# AirCond_P1_V2_0.net
KiCad netlist of a schematic drawn in Altium Designer
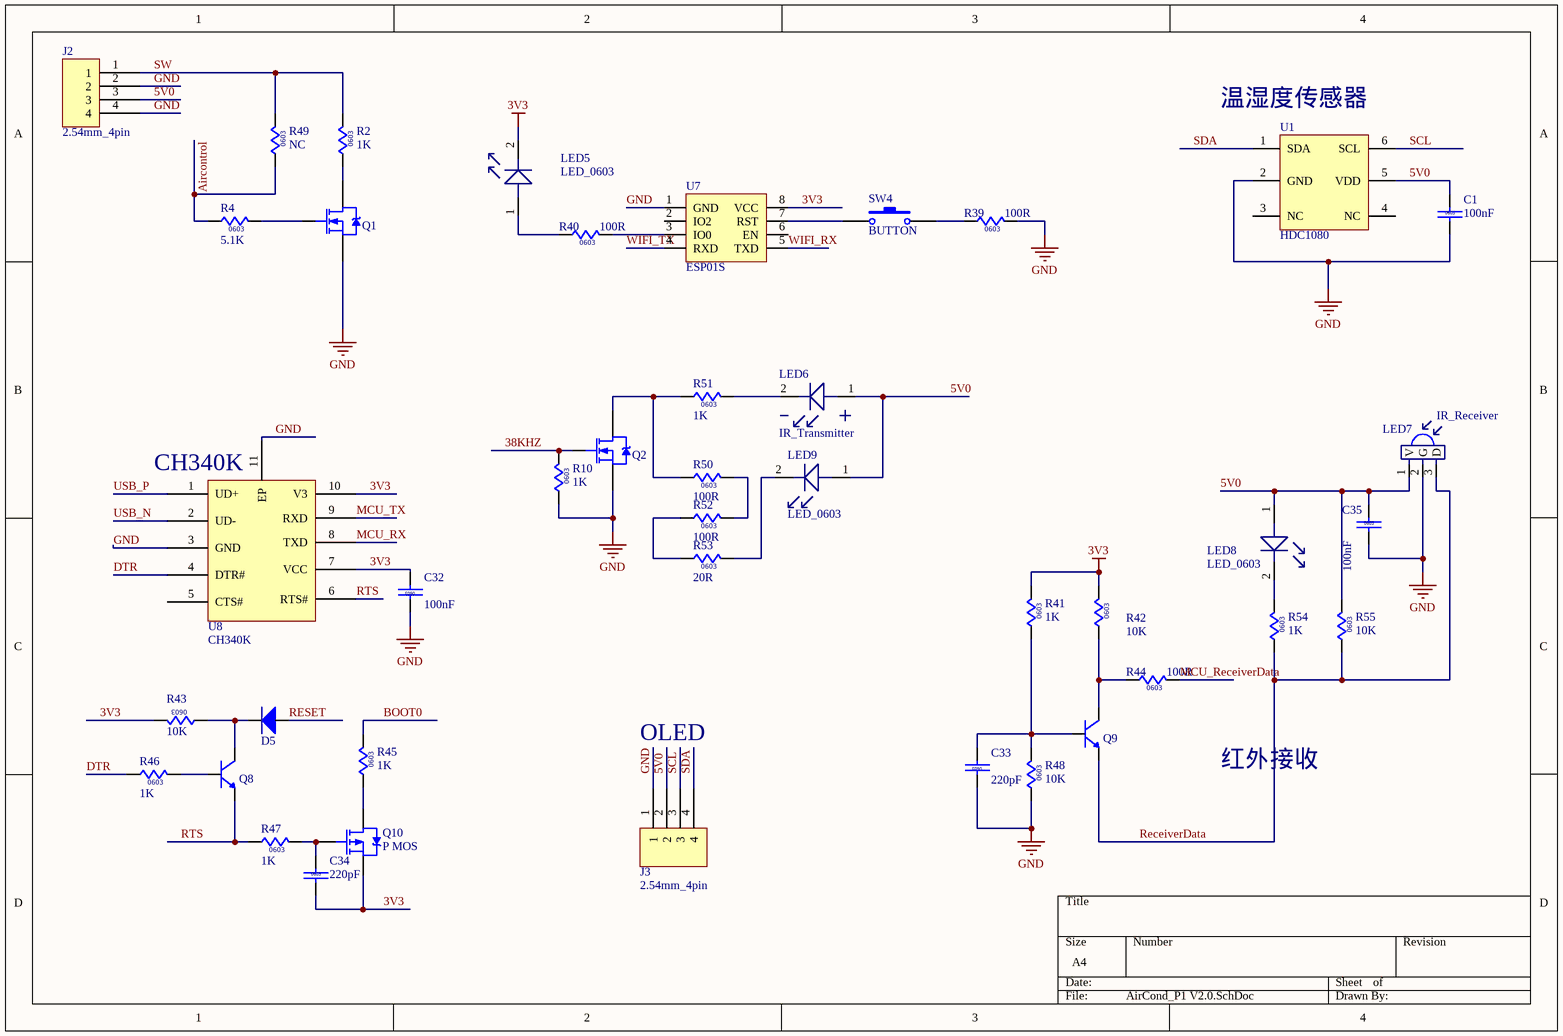
[diagram p0: AirCond_P1 V2.0.SchDoc]

(export (version "E")
  (design (tool "Eeschema 10.0.6"))
  (components
    (comp (ref "C1") (value "100nF") (footprint "0603/CAP") (libsource (lib "ZWC") (part "CAP/0603")))
    (comp (ref "C32") (value "100nF") (footprint "0603/CAP") (libsource (lib "ZWC") (part "CAP/0603")))
    (comp (ref "C33") (value "220pF") (footprint "0603/CAP") (libsource (lib "ZWC") (part "CAP/0603")))
    (comp (ref "C34") (value "220pF") (footprint "0603/CAP") (libsource (lib "ZWC") (part "CAP/0603")))
    (comp (ref "C35") (value "100nF") (footprint "0603/CAP") (libsource (lib "ZWC") (part "CAP/0603")))
    (comp (ref "D5") (value "S1M") (footprint "DO-214AC(SMA)") (libsource (lib "ZWC") (part "S1M")))
    (comp (ref "J2")
      (value "2.54mm_4pin")
      (footprint "2.54mm_4pin")
      (libsource (lib "MySelf") (part "2.54mm_4pin"))
    )
    (comp (ref "J3")
      (value "2.54mm_4pin")
      (footprint "2.54mm_4pin")
      (libsource (lib "") (part "2.54mm_4pin_1"))
    )
    (comp (ref "LED5") (value "LED_0603") (footprint "0603/RES") (libsource (lib "MySelf") (part "LED_0603")))
    (comp (ref "LED6")
      (value "IR_Transmitter")
      (footprint "2.54_2pin")
      (libsource (lib "MySelf") (part "IR_Transmitter"))
    )
    (comp (ref "LED7")
      (value "IR_Receiver")
      (footprint "2.54mm_3pin")
      (libsource (lib "MySelf") (part "IR_Receiver"))
    )
    (comp (ref "LED8") (value "LED_0603") (footprint "0603/RES") (libsource (lib "MySelf") (part "LED_0603")))
    (comp (ref "LED9") (value "LED_0603") (footprint "0603/RES") (libsource (lib "MySelf") (part "LED_0603")))
    (comp (ref "Q1") (value "NMOS") (footprint "SOT-23") (libsource (lib "ZWC") (part "N-MOSE")))
    (comp (ref "Q2") (value "NMOS") (footprint "SOT-23") (libsource (lib "ZWC") (part "N-MOSE")))
    (comp (ref "Q8") (value "BC817-16") (footprint "SOT-23") (libsource (lib "ZWC") (part "NPN")))
    (comp (ref "Q9") (value "BC817-16") (footprint "SOT-23") (libsource (lib "ZWC") (part "NPN")))
    (comp (ref "Q10")
      (value "P MOS")
      (footprint "SOT-23")
      (description "P-Channel Power MOSFET")
      (fields (field (name "PUBLISHER") "Altium Limited"))
      (libsource (lib "ZWC") (part "PMOS-3"))
    )
    (comp (ref "R2") (value "1K") (footprint "0603/RES") (libsource (lib "ZWC") (part "RES/0603")))
    (comp (ref "R4") (value "5.1K") (footprint "0603/RES") (libsource (lib "ZWC") (part "RES/0603")))
    (comp (ref "R10") (value "1K") (footprint "0603/RES") (libsource (lib "ZWC") (part "RES/0603")))
    (comp (ref "R39") (value "100R") (footprint "0603/RES") (libsource (lib "ZWC") (part "RES/0603")))
    (comp (ref "R40") (value "100R") (footprint "0603/RES") (libsource (lib "ZWC") (part "RES/0603")))
    (comp (ref "R41") (value "1K") (footprint "0603/RES") (libsource (lib "ZWC") (part "RES/0603")))
    (comp (ref "R42") (value "10K") (footprint "0603/RES") (libsource (lib "ZWC") (part "RES/0603")))
    (comp (ref "R43") (value "10K") (footprint "0603/RES") (libsource (lib "ZWC") (part "RES/0603")))
    (comp (ref "R44") (value "100R") (footprint "0603/RES") (libsource (lib "ZWC") (part "RES/0603")))
    (comp (ref "R45") (value "1K") (footprint "0603/RES") (libsource (lib "ZWC") (part "RES/0603")))
    (comp (ref "R46") (value "1K") (footprint "0603/RES") (libsource (lib "ZWC") (part "RES/0603")))
    (comp (ref "R47") (value "1K") (footprint "0603/RES") (libsource (lib "ZWC") (part "RES/0603")))
    (comp (ref "R48") (value "10K") (footprint "0603/RES") (libsource (lib "ZWC") (part "RES/0603")))
    (comp (ref "R49") (value "NC") (footprint "0603/RES") (libsource (lib "ZWC") (part "RES/0603")))
    (comp (ref "R50") (value "100R") (footprint "0603/RES") (libsource (lib "ZWC") (part "RES/0603")))
    (comp (ref "R51") (value "1K") (footprint "0603/RES") (libsource (lib "ZWC") (part "RES/0603")))
    (comp (ref "R52") (value "100R") (footprint "0603/RES") (libsource (lib "ZWC") (part "RES/0603")))
    (comp (ref "R53") (value "20R") (footprint "0603/RES") (libsource (lib "ZWC") (part "RES/0603")))
    (comp (ref "R54") (value "1K") (footprint "0603/RES") (libsource (lib "ZWC") (part "RES/0603")))
    (comp (ref "R55") (value "10K") (footprint "0603/RES") (libsource (lib "ZWC") (part "RES/0603")))
    (comp (ref "SW4") (value "BUTTON") (footprint "Key-D8mm") (libsource (lib "ZWC") (part "BUTTON_1")))
    (comp (ref "U1") (value "HDC1080") (footprint "HDC1080") (libsource (lib "MySelf") (part "HDC1080")))
    (comp (ref "U7") (value "ESP01S") (footprint "2.54MM_2X4PIN") (libsource (lib "MySelf") (part "ESP01S")))
    (comp (ref "U8") (value "CH340K") (footprint "ESSOP10") (libsource (lib "MySelf") (part "CH340K")))
  )
  (nets
    (net (code "1") (name "/5V0") (class "Default")
      (node (ref "C1") (pin "1") (pinfunction "1_1") (pintype "passive"))
      (node (ref "C35") (pin "1") (pinfunction "1_1") (pintype "passive"))
      (node (ref "J2") (pin "3") (pinfunction "3_3") (pintype "passive"))
      (node (ref "J3") (pin "2") (pinfunction "2_2") (pintype "passive"))
      (node (ref "LED6") (pin "1") (pinfunction "1_1") (pintype "passive"))
      (node (ref "LED7") (pin "1") (pinfunction "V_1") (pintype "passive"))
      (node (ref "LED8") (pin "1") (pinfunction "1_1") (pintype "passive"))
      (node (ref "LED9") (pin "1") (pinfunction "1_1") (pintype "passive"))
      (node (ref "R55") (pin "2") (pinfunction "2_2") (pintype "passive"))
      (node (ref "U1") (pin "5") (pinfunction "VDD_5") (pintype "passive"))
    )
    (net (code "2") (name "/38KHZ") (class "Default")
      (node (ref "Q2") (pin "1") (pinfunction "G_1") (pintype "passive"))
      (node (ref "R10") (pin "2") (pinfunction "2_2") (pintype "passive"))
    )
    (net (code "3") (name "/Aircontrol") (class "Default")
      (node (ref "R4") (pin "1") (pinfunction "1_1") (pintype "passive"))
      (node (ref "R49") (pin "1") (pinfunction "1_1") (pintype "passive"))
    )
    (net (code "4") (name "/BOOT0") (class "Default")
      (node (ref "R45") (pin "2") (pinfunction "2_2") (pintype "passive"))
    )
    (net (code "5") (name "/DTR") (class "Default")
      (node (ref "R46") (pin "1") (pinfunction "1_1") (pintype "passive"))
      (node (ref "U8") (pin "4") (pinfunction "DTR#_4") (pintype "passive"))
    )
    (net (code "6") (name "/MCU_RX") (class "Default")
      (node (ref "U8") (pin "8") (pinfunction "TXD_8") (pintype "passive"))
    )
    (net (code "7") (name "/MCU_ReceiverData") (class "Default")
      (node (ref "R44") (pin "2") (pinfunction "2_2") (pintype "passive"))
    )
    (net (code "8") (name "/MCU_TX") (class "Default")
      (node (ref "U8") (pin "9") (pinfunction "RXD_9") (pintype "passive"))
    )
    (net (code "9") (name "/RESET") (class "Default") (node (ref "D5") (pin "1") (pintype "passive")))
    (net (code "10") (name "/RTS") (class "Default")
      (node (ref "Q8") (pin "2") (pinfunction "E_2") (pintype "passive"))
      (node (ref "R47") (pin "1") (pinfunction "1_1") (pintype "passive"))
      (node (ref "U8") (pin "6") (pinfunction "RTS#_6") (pintype "passive"))
    )
    (net (code "11") (name "/ReceiverData") (class "Default")
      (node (ref "LED7") (pin "3") (pinfunction "D_3") (pintype "passive"))
      (node (ref "Q9") (pin "2") (pinfunction "E_2") (pintype "passive"))
      (node (ref "R54") (pin "1") (pinfunction "1_1") (pintype "passive"))
      (node (ref "R55") (pin "1") (pinfunction "1_1") (pintype "passive"))
    )
    (net (code "12") (name "/SCL") (class "Default")
      (node (ref "J3") (pin "3") (pinfunction "3_3") (pintype "passive"))
      (node (ref "U1") (pin "6") (pinfunction "SCL_6") (pintype "passive"))
    )
    (net (code "13") (name "/SDA") (class "Default")
      (node (ref "J3") (pin "4") (pinfunction "4_4") (pintype "passive"))
      (node (ref "U1") (pin "1") (pinfunction "SDA_1") (pintype "passive"))
    )
    (net (code "14") (name "/SW") (class "Default")
      (node (ref "J2") (pin "1") (pinfunction "1_1") (pintype "passive"))
      (node (ref "R2") (pin "2") (pinfunction "2_2") (pintype "passive"))
      (node (ref "R49") (pin "2") (pinfunction "2_2") (pintype "passive"))
    )
    (net (code "15") (name "/USB_N") (class "Default")
      (node (ref "U8") (pin "2") (pinfunction "UD-_2") (pintype "passive"))
    )
    (net (code "16") (name "/USB_P") (class "Default")
      (node (ref "U8") (pin "1") (pinfunction "UD+_1") (pintype "passive"))
    )
    (net (code "17") (name "/WIFI_RX") (class "Default")
      (node (ref "U7") (pin "5") (pinfunction "TXD_5") (pintype "passive"))
    )
    (net (code "18") (name "/WIFI_TX") (class "Default")
      (node (ref "U7") (pin "4") (pinfunction "RXD_4") (pintype "passive"))
    )
    (net (code "19") (name "3V3") (class "Default")
      (node (ref "C32") (pin "2") (pinfunction "2_2") (pintype "passive"))
      (node (ref "C34") (pin "2") (pinfunction "2_2") (pintype "passive"))
      (node (ref "LED5") (pin "2") (pinfunction "2_2") (pintype "passive"))
      (node (ref "Q10") (pin "2") (pinfunction "S_2") (pintype "passive"))
      (node (ref "R41") (pin "2") (pinfunction "2_2") (pintype "passive"))
      (node (ref "R42") (pin "2") (pinfunction "2_2") (pintype "passive"))
      (node (ref "R43") (pin "2") (pinfunction "2_2") (pintype "passive"))
      (node (ref "U7") (pin "8") (pinfunction "VCC_8") (pintype "passive"))
      (node (ref "U8") (pin "10") (pinfunction "V3_10") (pintype "passive"))
      (node (ref "U8") (pin "7") (pinfunction "VCC_7") (pintype "passive"))
    )
    (net (code "20") (name "GND") (class "Default")
      (node (ref "C1") (pin "2") (pinfunction "2_2") (pintype "passive"))
      (node (ref "C32") (pin "1") (pinfunction "1_1") (pintype "passive"))
      (node (ref "C33") (pin "1") (pinfunction "1_1") (pintype "passive"))
      (node (ref "C35") (pin "2") (pinfunction "2_2") (pintype "passive"))
      (node (ref "J2") (pin "2") (pinfunction "2_2") (pintype "passive"))
      (node (ref "J2") (pin "4") (pinfunction "4_4") (pintype "passive"))
      (node (ref "J3") (pin "1") (pinfunction "1_1") (pintype "passive"))
      (node (ref "LED7") (pin "2") (pinfunction "G_2") (pintype "passive"))
      (node (ref "Q1") (pin "2") (pinfunction "S_2") (pintype "passive"))
      (node (ref "Q2") (pin "2") (pinfunction "S_2") (pintype "passive"))
      (node (ref "R10") (pin "1") (pinfunction "1_1") (pintype "passive"))
      (node (ref "R39") (pin "2") (pinfunction "2_2") (pintype "passive"))
      (node (ref "R48") (pin "1") (pinfunction "1_1") (pintype "passive"))
      (node (ref "U1") (pin "2") (pinfunction "GND_2") (pintype "passive"))
      (node (ref "U7") (pin "1") (pinfunction "GND_1") (pintype "passive"))
      (node (ref "U8") (pin "11") (pinfunction "EP_11") (pintype "passive"))
      (node (ref "U8") (pin "3") (pinfunction "GND_3") (pintype "passive"))
    )
    (net (code "21") (name "Net-(LED5-Pad1)") (class "Default")
      (node (ref "LED5") (pin "1") (pinfunction "1_1") (pintype "passive"))
      (node (ref "R40") (pin "1") (pinfunction "1_1") (pintype "passive"))
    )
    (net (code "22") (name "Net-(LED6-Pad2)") (class "Default")
      (node (ref "LED6") (pin "2") (pinfunction "2_2") (pintype "passive"))
      (node (ref "R51") (pin "2") (pinfunction "2_2") (pintype "passive"))
    )
    (net (code "23") (name "Net-(LED8-Pad2)") (class "Default")
      (node (ref "LED8") (pin "2") (pinfunction "2_2") (pintype "passive"))
      (node (ref "R54") (pin "2") (pinfunction "2_2") (pintype "passive"))
    )
    (net (code "24") (name "Net-(LED9-Pad2)") (class "Default")
      (node (ref "LED9") (pin "2") (pinfunction "2_2") (pintype "passive"))
      (node (ref "R53") (pin "2") (pinfunction "2_2") (pintype "passive"))
    )
    (net (code "25") (name "Net-(Q1-D)") (class "Default")
      (node (ref "Q1") (pin "3") (pinfunction "D_3") (pintype "passive"))
      (node (ref "R2") (pin "1") (pinfunction "1_1") (pintype "passive"))
    )
    (net (code "26") (name "Net-(Q1-G)") (class "Default")
      (node (ref "Q1") (pin "1") (pinfunction "G_1") (pintype "passive"))
      (node (ref "R4") (pin "2") (pinfunction "2_2") (pintype "passive"))
    )
    (net (code "27") (name "Net-(Q2-D)") (class "Default")
      (node (ref "Q2") (pin "3") (pinfunction "D_3") (pintype "passive"))
      (node (ref "R50") (pin "1") (pinfunction "1_1") (pintype "passive"))
      (node (ref "R51") (pin "1") (pinfunction "1_1") (pintype "passive"))
    )
    (net (code "28") (name "Net-(Q8-B)") (class "Default")
      (node (ref "Q8") (pin "1") (pinfunction "B_1") (pintype "passive"))
      (node (ref "R46") (pin "2") (pinfunction "2_2") (pintype "passive"))
    )
    (net (code "29") (name "Net-(Q8-C)") (class "Default")
      (node (ref "D5") (pin "2") (pintype "passive"))
      (node (ref "Q8") (pin "3") (pinfunction "C_3") (pintype "passive"))
      (node (ref "R43") (pin "1") (pinfunction "1_1") (pintype "passive"))
    )
    (net (code "30") (name "Net-(Q9-B)") (class "Default")
      (node (ref "C33") (pin "2") (pinfunction "2_2") (pintype "passive"))
      (node (ref "Q9") (pin "1") (pinfunction "B_1") (pintype "passive"))
      (node (ref "R41") (pin "1") (pinfunction "1_1") (pintype "passive"))
      (node (ref "R48") (pin "2") (pinfunction "2_2") (pintype "passive"))
    )
    (net (code "31") (name "Net-(Q9-C)") (class "Default")
      (node (ref "Q9") (pin "3") (pinfunction "C_3") (pintype "passive"))
      (node (ref "R42") (pin "1") (pinfunction "1_1") (pintype "passive"))
      (node (ref "R44") (pin "1") (pinfunction "1_1") (pintype "passive"))
    )
    (net (code "32") (name "Net-(Q10-D)") (class "Default")
      (node (ref "Q10") (pin "3") (pinfunction "D_3") (pintype "passive"))
      (node (ref "R45") (pin "1") (pinfunction "1_1") (pintype "passive"))
    )
    (net (code "33") (name "Net-(Q10-G)") (class "Default")
      (node (ref "C34") (pin "1") (pinfunction "1_1") (pintype "passive"))
      (node (ref "Q10") (pin "1") (pinfunction "G_1") (pintype "passive"))
      (node (ref "R47") (pin "2") (pinfunction "2_2") (pintype "passive"))
    )
    (net (code "34") (name "Net-(R39-Pad1)") (class "Default")
      (node (ref "R39") (pin "1") (pinfunction "1_1") (pintype "passive"))
      (node (ref "SW4") (pin "2") (pinfunction "2_2") (pintype "passive"))
    )
    (net (code "35") (name "Net-(R50-Pad2)") (class "Default")
      (node (ref "R50") (pin "2") (pinfunction "2_2") (pintype "passive"))
      (node (ref "R52") (pin "2") (pinfunction "2_2") (pintype "passive"))
    )
    (net (code "36") (name "Net-(R52-Pad1)") (class "Default")
      (node (ref "R52") (pin "1") (pinfunction "1_1") (pintype "passive"))
      (node (ref "R53") (pin "1") (pinfunction "1_1") (pintype "passive"))
    )
    (net (code "37") (name "Net-(U7-IO0)") (class "Default")
      (node (ref "R40") (pin "2") (pinfunction "2_2") (pintype "passive"))
      (node (ref "U7") (pin "3") (pinfunction "IO0_3") (pintype "passive"))
    )
    (net (code "38") (name "Net-(U7-RST)") (class "Default")
      (node (ref "SW4") (pin "1") (pinfunction "1_1") (pintype "passive"))
      (node (ref "U7") (pin "7") (pinfunction "RST_7") (pintype "passive"))
    )
    (net (code "39") (name "unconnected-(U1-NC-Pad3)") (class "Default")
      (node (ref "U1") (pin "3") (pinfunction "NC_3") (pintype "passive"))
    )
    (net (code "40") (name "unconnected-(U1-NC-Pad4)") (class "Default")
      (node (ref "U1") (pin "4") (pinfunction "NC_4") (pintype "passive"))
    )
    (net (code "41") (name "unconnected-(U7-EN-Pad6)") (class "Default")
      (node (ref "U7") (pin "6") (pinfunction "EN_6") (pintype "passive"))
    )
    (net (code "42") (name "unconnected-(U7-IO2-Pad2)") (class "Default")
      (node (ref "U7") (pin "2") (pinfunction "IO2_2") (pintype "passive"))
    )
    (net (code "43") (name "unconnected-(U8-CTS#-Pad5)") (class "Default")
      (node (ref "U8") (pin "5") (pinfunction "CTS#_5") (pintype "passive"))
    )
  )
)
